# audio_sheet.net
KiCad netlist of a schematic drawn in Altium Designer
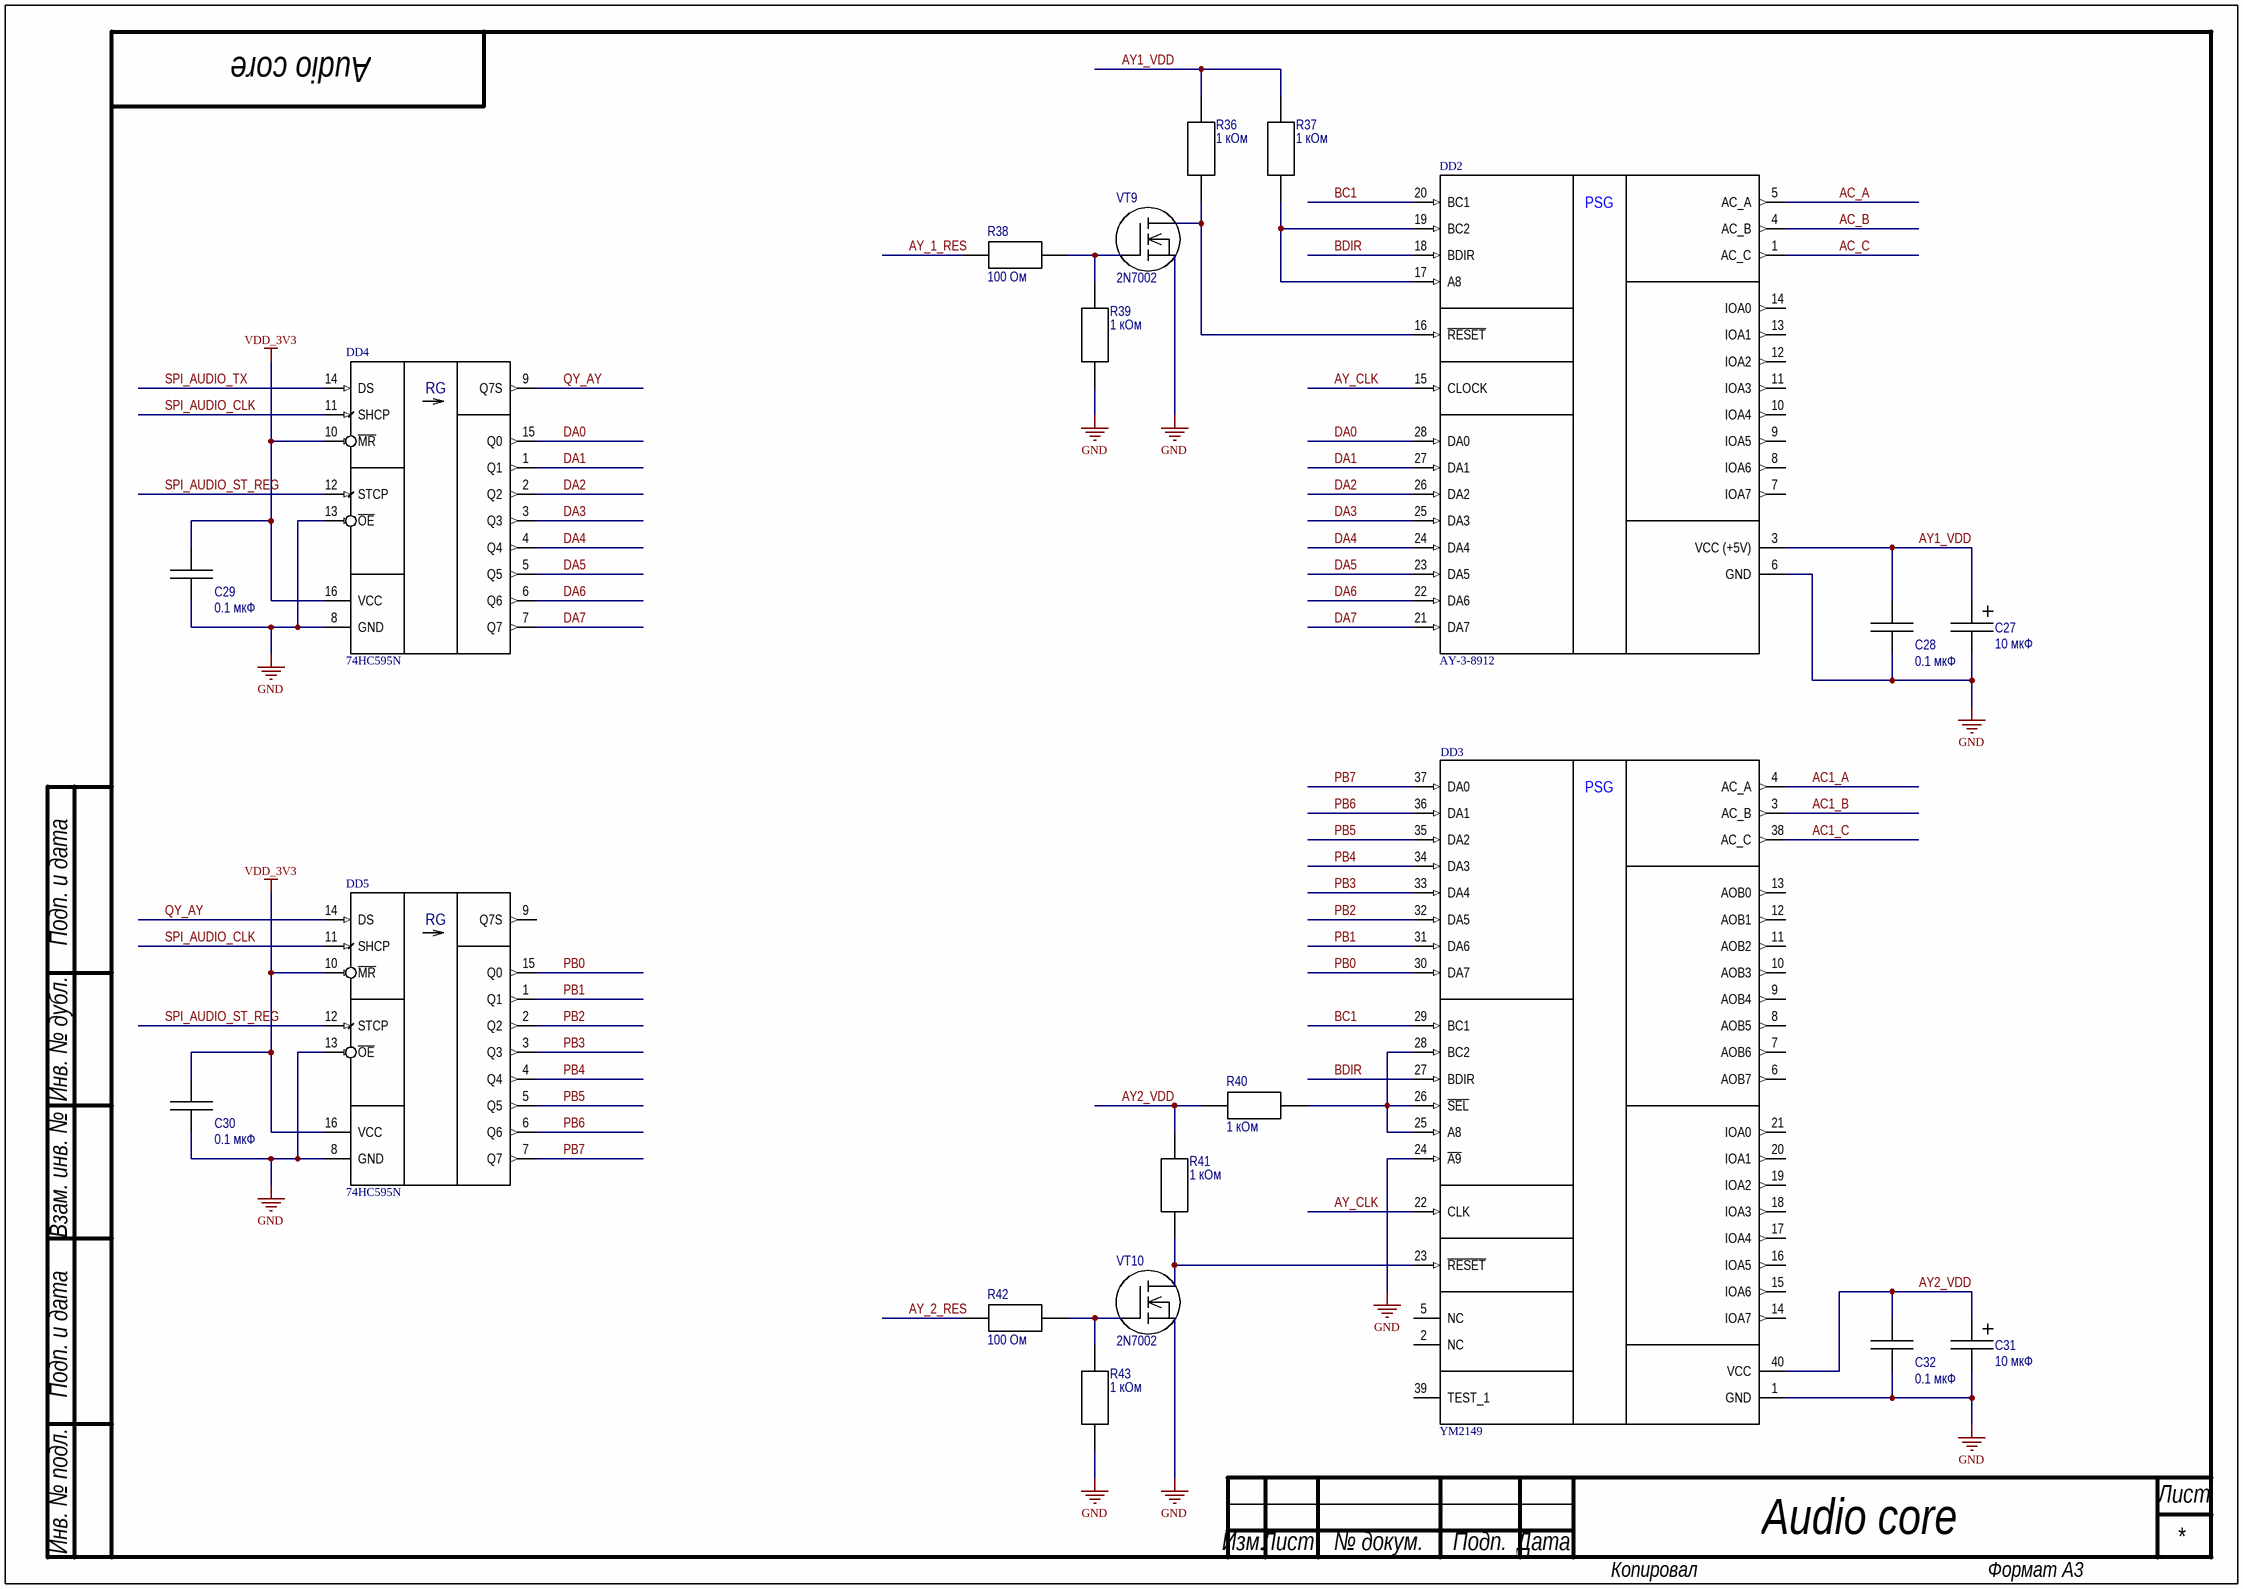
[diagram p0: audio_sheet.SchDoc]

(export (version "E")
  (design (tool "Eeschema 10.0.6"))
  (components
    (comp (ref "C27")
      (value "10 мкФ")
      (footprint "C TAN_C")
      (description "SMD Tantalium Capacitor C")
      (fields
        (field (name "TOLERANCE") "/Укажите допуск в процентах/")
        (field (name "MANUFACTURER") "/Укажите компанию-производителя/")
      )
      (libsource (lib "my_lib") (part "CAP TAN_C"))
    )
    (comp (ref "C28")
      (value "0.1 мкФ")
      (footprint "C 1206")
      (description "SMD Capacitor 1206")
      (fields
        (field (name "TOLERANCE") "/Укажите допуск в процентах/")
        (field (name "MANUFACTURER") "/Укажите компанию-производителя/")
      )
      (libsource (lib "my_lib") (part "CAP 1206"))
    )
    (comp (ref "C29")
      (value "0.1 мкФ")
      (footprint "C 1206")
      (description "SMD Capacitor 1206")
      (fields
        (field (name "TOLERANCE") "/Укажите допуск в процентах/")
        (field (name "MANUFACTURER") "/Укажите компанию-производителя/")
      )
      (libsource (lib "my_lib") (part "CAP 1206"))
    )
    (comp (ref "C30")
      (value "0.1 мкФ")
      (footprint "C 1206")
      (description "SMD Capacitor 1206")
      (fields
        (field (name "TOLERANCE") "/Укажите допуск в процентах/")
        (field (name "MANUFACTURER") "/Укажите компанию-производителя/")
      )
      (libsource (lib "my_lib") (part "CAP 1206"))
    )
    (comp (ref "C31")
      (value "10 мкФ")
      (footprint "C TAN_C")
      (description "SMD Tantalium Capacitor C")
      (fields
        (field (name "TOLERANCE") "/Укажите допуск в процентах/")
        (field (name "MANUFACTURER") "/Укажите компанию-производителя/")
      )
      (libsource (lib "my_lib") (part "CAP TAN_C"))
    )
    (comp (ref "C32")
      (value "0.1 мкФ")
      (footprint "C 1206")
      (description "SMD Capacitor 1206")
      (fields
        (field (name "TOLERANCE") "/Укажите допуск в процентах/")
        (field (name "MANUFACTURER") "/Укажите компанию-производителя/")
      )
      (libsource (lib "my_lib") (part "CAP 1206"))
    )
    (comp (ref "DD2") (value "AY-3-8912") (footprint "DIP-28") (libsource (lib "my_lib") (part "AY-3-8912")))
    (comp (ref "DD3") (value "YM2149") (footprint "DIP-40") (libsource (lib "my_lib") (part "YM2149")))
    (comp (ref "DD4") (value "74HC595N") (footprint "SO16") (libsource (lib "my_lib") (part "74HC595N")))
    (comp (ref "DD5") (value "74HC595N") (footprint "SO16") (libsource (lib "my_lib") (part "74HC595N")))
    (comp (ref "R36") (value "1 кОм") (footprint "RES 0402") (libsource (lib "my_lib") (part "RES 0402")))
    (comp (ref "R37") (value "1 кОм") (footprint "RES 0402") (libsource (lib "my_lib") (part "RES 0402")))
    (comp (ref "R38") (value "100 Ом") (footprint "RES 0402") (libsource (lib "my_lib") (part "RES 0402")))
    (comp (ref "R39") (value "1 кОм") (footprint "RES 0402") (libsource (lib "my_lib") (part "RES 0402")))
    (comp (ref "R40") (value "1 кОм") (footprint "RES 0402") (libsource (lib "my_lib") (part "RES 0402")))
    (comp (ref "R41") (value "1 кОм") (footprint "RES 0402") (libsource (lib "my_lib") (part "RES 0402")))
    (comp (ref "R42") (value "100 Ом") (footprint "RES 0402") (libsource (lib "my_lib") (part "RES 0402")))
    (comp (ref "R43") (value "1 кОм") (footprint "RES 0402") (libsource (lib "my_lib") (part "RES 0402")))
    (comp (ref "VT9")
      (value "2N7002")
      (footprint "SOT-23")
      (description "60 V, 300 mA N-channel Trench MOSFET")
      (fields (field (name "MANUFACTURER") "NXP"))
      (libsource (lib "my_lib") (part "2N7002"))
    )
    (comp (ref "VT10")
      (value "2N7002")
      (footprint "SOT-23")
      (description "60 V, 300 mA N-channel Trench MOSFET")
      (fields (field (name "MANUFACTURER") "NXP"))
      (libsource (lib "my_lib") (part "2N7002"))
    )
  )
  (nets
    (net (code "1") (name "/AC1_A") (class "Default")
      (node (ref "DD3") (pin "4") (pinfunction "AC_A_4") (pintype "output"))
    )
    (net (code "2") (name "/AC1_B") (class "Default")
      (node (ref "DD3") (pin "3") (pinfunction "AC_B_3") (pintype "output"))
    )
    (net (code "3") (name "/AC1_C") (class "Default")
      (node (ref "DD3") (pin "38") (pinfunction "AC_C_38") (pintype "output"))
    )
    (net (code "4") (name "/AC_A") (class "Default")
      (node (ref "DD2") (pin "5") (pinfunction "AC_A_5") (pintype "output"))
    )
    (net (code "5") (name "/AC_B") (class "Default")
      (node (ref "DD2") (pin "4") (pinfunction "AC_B_4") (pintype "output"))
    )
    (net (code "6") (name "/AC_C") (class "Default")
      (node (ref "DD2") (pin "1") (pinfunction "AC_C_1") (pintype "output"))
    )
    (net (code "7") (name "/AY1_VDD") (class "Default")
      (node (ref "C27") (pin "1") (pinfunction "1_1") (pintype "passive"))
      (node (ref "C28") (pin "1") (pinfunction "1_1") (pintype "passive"))
      (node (ref "DD2") (pin "3") (pinfunction "VCC_(+5V)_3") (pintype "power_in"))
      (node (ref "R36") (pin "1") (pinfunction "1_1") (pintype "passive"))
      (node (ref "R37") (pin "1") (pinfunction "1_1") (pintype "passive"))
    )
    (net (code "8") (name "/AY2_VDD") (class "Default")
      (node (ref "C31") (pin "1") (pinfunction "1_1") (pintype "passive"))
      (node (ref "C32") (pin "1") (pinfunction "1_1") (pintype "passive"))
      (node (ref "DD3") (pin "40") (pinfunction "VCC_40") (pintype "power_in"))
      (node (ref "R40") (pin "1") (pinfunction "1_1") (pintype "passive"))
      (node (ref "R41") (pin "1") (pinfunction "1_1") (pintype "passive"))
    )
    (net (code "9") (name "/AY_1_RES") (class "Default")
      (node (ref "R38") (pin "1") (pinfunction "1_1") (pintype "passive"))
    )
    (net (code "10") (name "/AY_2_RES") (class "Default")
      (node (ref "R42") (pin "1") (pinfunction "1_1") (pintype "passive"))
    )
    (net (code "11") (name "/AY_CLK") (class "Default")
      (node (ref "DD2") (pin "15") (pinfunction "CLOCK_15") (pintype "input"))
      (node (ref "DD3") (pin "22") (pinfunction "CLK_22") (pintype "input"))
    )
    (net (code "12") (name "/BC1") (class "Default")
      (node (ref "DD2") (pin "20") (pinfunction "BC1_20") (pintype "input"))
      (node (ref "DD3") (pin "29") (pinfunction "BC1_29") (pintype "input"))
    )
    (net (code "13") (name "/BDIR") (class "Default")
      (node (ref "DD2") (pin "18") (pinfunction "BDIR_18") (pintype "input"))
      (node (ref "DD3") (pin "27") (pinfunction "BDIR_27") (pintype "input"))
    )
    (net (code "14") (name "/DA0") (class "Default")
      (node (ref "DD2") (pin "28") (pinfunction "DA0_28") (pintype "input"))
      (node (ref "DD4") (pin "15") (pinfunction "Q0_15") (pintype "output"))
    )
    (net (code "15") (name "/DA1") (class "Default")
      (node (ref "DD2") (pin "27") (pinfunction "DA1_27") (pintype "input"))
      (node (ref "DD4") (pin "1") (pinfunction "Q1_1") (pintype "output"))
    )
    (net (code "16") (name "/DA2") (class "Default")
      (node (ref "DD2") (pin "26") (pinfunction "DA2_26") (pintype "input"))
      (node (ref "DD4") (pin "2") (pinfunction "Q2_2") (pintype "output"))
    )
    (net (code "17") (name "/DA3") (class "Default")
      (node (ref "DD2") (pin "25") (pinfunction "DA3_25") (pintype "input"))
      (node (ref "DD4") (pin "3") (pinfunction "Q3_3") (pintype "output"))
    )
    (net (code "18") (name "/DA4") (class "Default")
      (node (ref "DD2") (pin "24") (pinfunction "DA4_24") (pintype "input"))
      (node (ref "DD4") (pin "4") (pinfunction "Q4_4") (pintype "output"))
    )
    (net (code "19") (name "/DA5") (class "Default")
      (node (ref "DD2") (pin "23") (pinfunction "DA5_23") (pintype "input"))
      (node (ref "DD4") (pin "5") (pinfunction "Q5_5") (pintype "output"))
    )
    (net (code "20") (name "/DA6") (class "Default")
      (node (ref "DD2") (pin "22") (pinfunction "DA6_22") (pintype "input"))
      (node (ref "DD4") (pin "6") (pinfunction "Q6_6") (pintype "output"))
    )
    (net (code "21") (name "/DA7") (class "Default")
      (node (ref "DD2") (pin "21") (pinfunction "DA7_21") (pintype "input"))
      (node (ref "DD4") (pin "7") (pinfunction "Q7_7") (pintype "output"))
    )
    (net (code "22") (name "/PB0") (class "Default")
      (node (ref "DD3") (pin "30") (pinfunction "DA7_30") (pintype "input"))
      (node (ref "DD5") (pin "15") (pinfunction "Q0_15") (pintype "output"))
    )
    (net (code "23") (name "/PB1") (class "Default")
      (node (ref "DD3") (pin "31") (pinfunction "DA6_31") (pintype "input"))
      (node (ref "DD5") (pin "1") (pinfunction "Q1_1") (pintype "output"))
    )
    (net (code "24") (name "/PB2") (class "Default")
      (node (ref "DD3") (pin "32") (pinfunction "DA5_32") (pintype "input"))
      (node (ref "DD5") (pin "2") (pinfunction "Q2_2") (pintype "output"))
    )
    (net (code "25") (name "/PB3") (class "Default")
      (node (ref "DD3") (pin "33") (pinfunction "DA4_33") (pintype "input"))
      (node (ref "DD5") (pin "3") (pinfunction "Q3_3") (pintype "output"))
    )
    (net (code "26") (name "/PB4") (class "Default")
      (node (ref "DD3") (pin "34") (pinfunction "DA3_34") (pintype "input"))
      (node (ref "DD5") (pin "4") (pinfunction "Q4_4") (pintype "output"))
    )
    (net (code "27") (name "/PB5") (class "Default")
      (node (ref "DD3") (pin "35") (pinfunction "DA2_35") (pintype "input"))
      (node (ref "DD5") (pin "5") (pinfunction "Q5_5") (pintype "output"))
    )
    (net (code "28") (name "/PB6") (class "Default")
      (node (ref "DD3") (pin "36") (pinfunction "DA1_36") (pintype "input"))
      (node (ref "DD5") (pin "6") (pinfunction "Q6_6") (pintype "output"))
    )
    (net (code "29") (name "/PB7") (class "Default")
      (node (ref "DD3") (pin "37") (pinfunction "DA0_37") (pintype "input"))
      (node (ref "DD5") (pin "7") (pinfunction "Q7_7") (pintype "output"))
    )
    (net (code "30") (name "/QY_AY") (class "Default")
      (node (ref "DD4") (pin "9") (pinfunction "Q7S_9") (pintype "output"))
      (node (ref "DD5") (pin "14") (pinfunction "DS_14") (pintype "input"))
    )
    (net (code "31") (name "/SPI_AUDIO_CLK") (class "Default")
      (node (ref "DD4") (pin "11") (pinfunction "SHCP_11") (pintype "input"))
      (node (ref "DD5") (pin "11") (pinfunction "SHCP_11") (pintype "input"))
    )
    (net (code "32") (name "/SPI_AUDIO_ST_REG") (class "Default")
      (node (ref "DD4") (pin "12") (pinfunction "STCP_12") (pintype "input"))
      (node (ref "DD5") (pin "12") (pinfunction "STCP_12") (pintype "input"))
    )
    (net (code "33") (name "/SPI_AUDIO_TX") (class "Default")
      (node (ref "DD4") (pin "14") (pinfunction "DS_14") (pintype "input"))
    )
    (net (code "34") (name "GND") (class "Default")
      (node (ref "C27") (pin "2") (pinfunction "2_2") (pintype "passive"))
      (node (ref "C28") (pin "2") (pinfunction "2_2") (pintype "passive"))
      (node (ref "C29") (pin "2") (pinfunction "2_2") (pintype "passive"))
      (node (ref "C30") (pin "2") (pinfunction "2_2") (pintype "passive"))
      (node (ref "C31") (pin "2") (pinfunction "2_2") (pintype "passive"))
      (node (ref "C32") (pin "2") (pinfunction "2_2") (pintype "passive"))
      (node (ref "DD2") (pin "6") (pinfunction "GND_6") (pintype "power_in"))
      (node (ref "DD3") (pin "1") (pinfunction "GND_1") (pintype "power_in"))
      (node (ref "DD3") (pin "24") (pinfunction "~{A9}_24") (pintype "input"))
      (node (ref "DD4") (pin "13") (pinfunction "~{OE}_13") (pintype "input"))
      (node (ref "DD4") (pin "8") (pinfunction "GND_8") (pintype "power_in"))
      (node (ref "DD5") (pin "13") (pinfunction "~{OE}_13") (pintype "input"))
      (node (ref "DD5") (pin "8") (pinfunction "GND_8") (pintype "power_in"))
      (node (ref "R39") (pin "2") (pinfunction "2_2") (pintype "passive"))
      (node (ref "R43") (pin "2") (pinfunction "2_2") (pintype "passive"))
      (node (ref "VT10") (pin "2") (pinfunction "S_2") (pintype "passive"))
      (node (ref "VT9") (pin "2") (pinfunction "S_2") (pintype "passive"))
    )
    (net (code "35") (name "Net-(DD2-A8)") (class "Default")
      (node (ref "DD2") (pin "17") (pinfunction "A8_17") (pintype "input"))
      (node (ref "DD2") (pin "19") (pinfunction "BC2_19") (pintype "input"))
      (node (ref "R37") (pin "2") (pinfunction "2_2") (pintype "passive"))
    )
    (net (code "36") (name "Net-(DD2-~{RESET})") (class "Default")
      (node (ref "DD2") (pin "16") (pinfunction "~{RESET}_16") (pintype "input"))
      (node (ref "R36") (pin "2") (pinfunction "2_2") (pintype "passive"))
      (node (ref "VT9") (pin "3") (pinfunction "D_3") (pintype "passive"))
    )
    (net (code "37") (name "Net-(DD3-A8)") (class "Default")
      (node (ref "DD3") (pin "25") (pinfunction "A8_25") (pintype "input"))
      (node (ref "DD3") (pin "26") (pinfunction "~{SEL}_26") (pintype "input"))
      (node (ref "DD3") (pin "28") (pinfunction "BC2_28") (pintype "input"))
      (node (ref "R40") (pin "2") (pinfunction "2_2") (pintype "passive"))
    )
    (net (code "38") (name "Net-(DD3-~{RESET})") (class "Default")
      (node (ref "DD3") (pin "23") (pinfunction "~{RESET}_23") (pintype "input"))
      (node (ref "R41") (pin "2") (pinfunction "2_2") (pintype "passive"))
      (node (ref "VT10") (pin "3") (pinfunction "D_3") (pintype "passive"))
    )
    (net (code "39") (name "Net-(VT9-G)") (class "Default")
      (node (ref "R38") (pin "2") (pinfunction "2_2") (pintype "passive"))
      (node (ref "R39") (pin "1") (pinfunction "1_1") (pintype "passive"))
      (node (ref "VT9") (pin "1") (pinfunction "G_1") (pintype "passive"))
    )
    (net (code "40") (name "Net-(VT10-G)") (class "Default")
      (node (ref "R42") (pin "2") (pinfunction "2_2") (pintype "passive"))
      (node (ref "R43") (pin "1") (pinfunction "1_1") (pintype "passive"))
      (node (ref "VT10") (pin "1") (pinfunction "G_1") (pintype "passive"))
    )
    (net (code "41") (name "VDD_3V3") (class "Default")
      (node (ref "C29") (pin "1") (pinfunction "1_1") (pintype "passive"))
      (node (ref "C30") (pin "1") (pinfunction "1_1") (pintype "passive"))
      (node (ref "DD4") (pin "10") (pinfunction "~{MR}_10") (pintype "input"))
      (node (ref "DD4") (pin "16") (pinfunction "VCC_16") (pintype "power_in"))
      (node (ref "DD5") (pin "10") (pinfunction "~{MR}_10") (pintype "input"))
      (node (ref "DD5") (pin "16") (pinfunction "VCC_16") (pintype "power_in"))
    )
    (net (code "42") (name "unconnected-(DD2-IOA0-Pad14)") (class "Default")
      (node (ref "DD2") (pin "14") (pinfunction "IOA0_14") (pintype "output"))
    )
    (net (code "43") (name "unconnected-(DD2-IOA1-Pad13)") (class "Default")
      (node (ref "DD2") (pin "13") (pinfunction "IOA1_13") (pintype "output"))
    )
    (net (code "44") (name "unconnected-(DD2-IOA2-Pad12)") (class "Default")
      (node (ref "DD2") (pin "12") (pinfunction "IOA2_12") (pintype "output"))
    )
    (net (code "45") (name "unconnected-(DD2-IOA3-Pad11)") (class "Default")
      (node (ref "DD2") (pin "11") (pinfunction "IOA3_11") (pintype "output"))
    )
    (net (code "46") (name "unconnected-(DD2-IOA4-Pad10)") (class "Default")
      (node (ref "DD2") (pin "10") (pinfunction "IOA4_10") (pintype "output"))
    )
    (net (code "47") (name "unconnected-(DD2-IOA5-Pad9)") (class "Default")
      (node (ref "DD2") (pin "9") (pinfunction "IOA5_9") (pintype "output"))
    )
    (net (code "48") (name "unconnected-(DD2-IOA6-Pad8)") (class "Default")
      (node (ref "DD2") (pin "8") (pinfunction "IOA6_8") (pintype "output"))
    )
    (net (code "49") (name "unconnected-(DD2-IOA7-Pad7)") (class "Default")
      (node (ref "DD2") (pin "7") (pinfunction "IOA7_7") (pintype "output"))
    )
    (net (code "50") (name "unconnected-(DD3-AOB0-Pad13)") (class "Default")
      (node (ref "DD3") (pin "13") (pinfunction "AOB0_13") (pintype "output"))
    )
    (net (code "51") (name "unconnected-(DD3-AOB1-Pad12)") (class "Default")
      (node (ref "DD3") (pin "12") (pinfunction "AOB1_12") (pintype "output"))
    )
    (net (code "52") (name "unconnected-(DD3-AOB2-Pad11)") (class "Default")
      (node (ref "DD3") (pin "11") (pinfunction "AOB2_11") (pintype "output"))
    )
    (net (code "53") (name "unconnected-(DD3-AOB3-Pad10)") (class "Default")
      (node (ref "DD3") (pin "10") (pinfunction "AOB3_10") (pintype "output"))
    )
    (net (code "54") (name "unconnected-(DD3-AOB4-Pad9)") (class "Default")
      (node (ref "DD3") (pin "9") (pinfunction "AOB4_9") (pintype "output"))
    )
    (net (code "55") (name "unconnected-(DD3-AOB5-Pad8)") (class "Default")
      (node (ref "DD3") (pin "8") (pinfunction "AOB5_8") (pintype "output"))
    )
    (net (code "56") (name "unconnected-(DD3-AOB6-Pad7)") (class "Default")
      (node (ref "DD3") (pin "7") (pinfunction "AOB6_7") (pintype "output"))
    )
    (net (code "57") (name "unconnected-(DD3-AOB7-Pad6)") (class "Default")
      (node (ref "DD3") (pin "6") (pinfunction "AOB7_6") (pintype "output"))
    )
    (net (code "58") (name "unconnected-(DD3-IOA0-Pad21)") (class "Default")
      (node (ref "DD3") (pin "21") (pinfunction "IOA0_21") (pintype "output"))
    )
    (net (code "59") (name "unconnected-(DD3-IOA1-Pad20)") (class "Default")
      (node (ref "DD3") (pin "20") (pinfunction "IOA1_20") (pintype "output"))
    )
    (net (code "60") (name "unconnected-(DD3-IOA2-Pad19)") (class "Default")
      (node (ref "DD3") (pin "19") (pinfunction "IOA2_19") (pintype "output"))
    )
    (net (code "61") (name "unconnected-(DD3-IOA3-Pad18)") (class "Default")
      (node (ref "DD3") (pin "18") (pinfunction "IOA3_18") (pintype "output"))
    )
    (net (code "62") (name "unconnected-(DD3-IOA4-Pad17)") (class "Default")
      (node (ref "DD3") (pin "17") (pinfunction "IOA4_17") (pintype "output"))
    )
    (net (code "63") (name "unconnected-(DD3-IOA5-Pad16)") (class "Default")
      (node (ref "DD3") (pin "16") (pinfunction "IOA5_16") (pintype "output"))
    )
    (net (code "64") (name "unconnected-(DD3-IOA6-Pad15)") (class "Default")
      (node (ref "DD3") (pin "15") (pinfunction "IOA6_15") (pintype "output"))
    )
    (net (code "65") (name "unconnected-(DD3-IOA7-Pad14)") (class "Default")
      (node (ref "DD3") (pin "14") (pinfunction "IOA7_14") (pintype "output"))
    )
    (net (code "66") (name "unconnected-(DD3-NC-Pad2)") (class "Default")
      (node (ref "DD3") (pin "2") (pinfunction "NC_2") (pintype "passive"))
    )
    (net (code "67") (name "unconnected-(DD3-NC-Pad5)") (class "Default")
      (node (ref "DD3") (pin "5") (pinfunction "NC_5") (pintype "passive"))
    )
    (net (code "68") (name "unconnected-(DD3-TEST_1-Pad39)") (class "Default")
      (node (ref "DD3") (pin "39") (pinfunction "TEST_1_39") (pintype "passive"))
    )
    (net (code "69") (name "unconnected-(DD5-Q7S-Pad9)") (class "Default")
      (node (ref "DD5") (pin "9") (pinfunction "Q7S_9") (pintype "output"))
    )
  )
)
